# 3V3_REG.net
KiCad netlist of a schematic drawn in Altium Designer
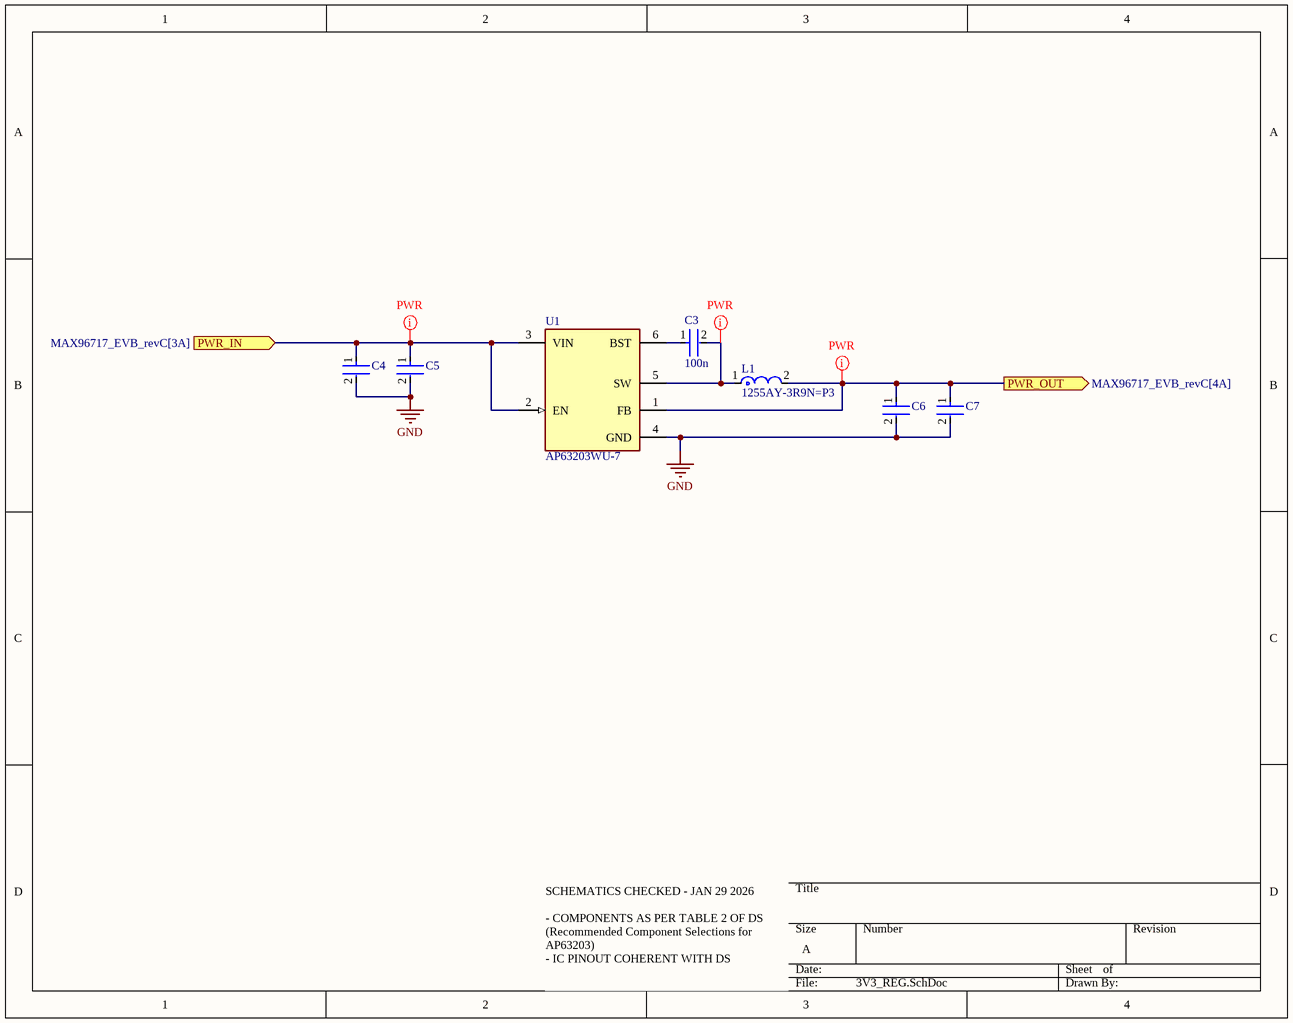
[diagram p0: 3V3_REG.SchDoc]

(export (version "E")
  (design (tool "Eeschema 10.0.6"))
  (components
    (comp (ref "C3")
      (value "100n")
      (footprint "FP-0402-L_1_0_0_05-W_0_5-IPC_A")
      (description "LARGE PADS, 0402 CAP, CHANGE COMMENT TO MATCH REAL P/N")
      (libsource (lib "Space Concordia") (part "b4654b650e69147ec39a6b967a45e02"))
    )
    (comp (ref "C4")
      (value "12103D106KAT2A")
      (footprint "FP-1210-L_3_3_0_4-W_2_5_0-MFG")
      (description "General Purpose Ceramic Capacitor, 1210, 10uF, 10%, X5R, 15%, 25V")
      (fields (field (name "VOLTAGE") "25V") (field (name "TOLERANCE") "10%"))
      (libsource (lib "Altium Content Vault") (part "b4654b650e69147ec39a6b967a45e02"))
    )
    (comp (ref "C5")
      (value "DNP")
      (footprint "FP-1210-L_3_3_0_4-W_2_5_0-MFG")
      (description "General Purpose Ceramic Capacitor, 1210, 10uF, 10%, X5R, 15%, 25V")
      (fields (field (name "VOLTAGE") "25V") (field (name "TOLERANCE") "10%"))
      (libsource (lib "Altium Content Vault") (part "b4654b650e69147ec39a6b967a45e02"))
    )
    (comp (ref "C6")
      (value "GRM21BR61E226ME44L")
      (footprint "FP-GRM21B-0_2-e0_2_0_7-IPC_B")
      (description "Chip Multilayer Ceramic Capacitors for General Purpose, 0805, 22uF, X5R, 15%, 20%, 25V")
      (fields (field (name "TOLERANCE") "20%") (field (name "VOLTAGE") "25V"))
      (libsource (lib "Altium Content Vault") (part "b4654b650e69147ec39a6b967a45e02"))
    )
    (comp (ref "C7")
      (value "GRM21BR61E226ME44L")
      (footprint "FP-GRM21B-0_2-e0_2_0_7-IPC_B")
      (description "Chip Multilayer Ceramic Capacitors for General Purpose, 0805, 22uF, X5R, 15%, 20%, 25V")
      (fields (field (name "TOLERANCE") "20%") (field (name "VOLTAGE") "25V"))
      (libsource (lib "Altium Content Vault") (part "b4654b650e69147ec39a6b967a45e02"))
    )
    (comp (ref "L1")
      (value "1255AY-3R9N=P3")
      (footprint "FP-DG6045C-MFG")
      (description "Shielded Wirewound Inductor 3.9uH 30% 4200mA 0.0264Ω SMD")
      (fields (field (name "TOLERANCE") "30%"))
      (libsource (lib "Altium Content Vault") (part "4cc4b267dca4c8e51f7102f422741d8"))
    )
    (comp (ref "U1")
      (value "AP63203WU-7")
      (footprint "FP-TSOT26-MFG")
      (description "IC REG BUCK 3.3V 2A TSOT26")
      (fields
        (field (name "MANUFACTURER") "Diodes Inc.")
        (field (name "OCTOPART") "https://octopart.com/ap63203wu-7-diodes+inc.-98099550")
      )
      (libsource (lib "Altium Content Vault") (part "0e61c2974d7114b43f01ef96ae2e524"))
    )
  )
  (nets
    (net (code "1") (name "/PWR_IN") (class "Default")
      (node (ref "C4") (pin "1") (pinfunction "1_1") (pintype "passive"))
      (node (ref "C5") (pin "1") (pinfunction "1_1") (pintype "passive"))
      (node (ref "U1") (pin "2") (pinfunction "EN_2") (pintype "input"))
      (node (ref "U1") (pin "3") (pinfunction "VIN_3") (pintype "power_in"))
    )
    (net (code "2") (name "/PWR_OUT") (class "Default")
      (node (ref "C6") (pin "1") (pinfunction "1_1") (pintype "passive"))
      (node (ref "C7") (pin "1") (pinfunction "1_1") (pintype "passive"))
      (node (ref "L1") (pin "2") (pinfunction "2_2") (pintype "passive"))
      (node (ref "U1") (pin "1") (pinfunction "FB_1") (pintype "passive"))
    )
    (net (code "3") (name "GND") (class "Default")
      (node (ref "C4") (pin "2") (pinfunction "2_2") (pintype "passive"))
      (node (ref "C5") (pin "2") (pinfunction "2_2") (pintype "passive"))
      (node (ref "C6") (pin "2") (pinfunction "2_2") (pintype "passive"))
      (node (ref "C7") (pin "2") (pinfunction "2_2") (pintype "passive"))
      (node (ref "U1") (pin "4") (pinfunction "GND_4") (pintype "power_in"))
    )
    (net (code "4") (name "Net-(U1-BST)") (class "Default")
      (node (ref "C3") (pin "1") (pinfunction "1_1") (pintype "passive"))
      (node (ref "U1") (pin "6") (pinfunction "BST_6") (pintype "passive"))
    )
    (net (code "5") (name "Net-(U1-SW)") (class "Default")
      (node (ref "C3") (pin "2") (pinfunction "2_2") (pintype "passive"))
      (node (ref "L1") (pin "1") (pinfunction "1_1") (pintype "passive"))
      (node (ref "U1") (pin "5") (pinfunction "SW_5") (pintype "passive"))
    )
  )
)
